# geiger_lora_edit3.net
KiCad netlist of a schematic drawn in EAGLE
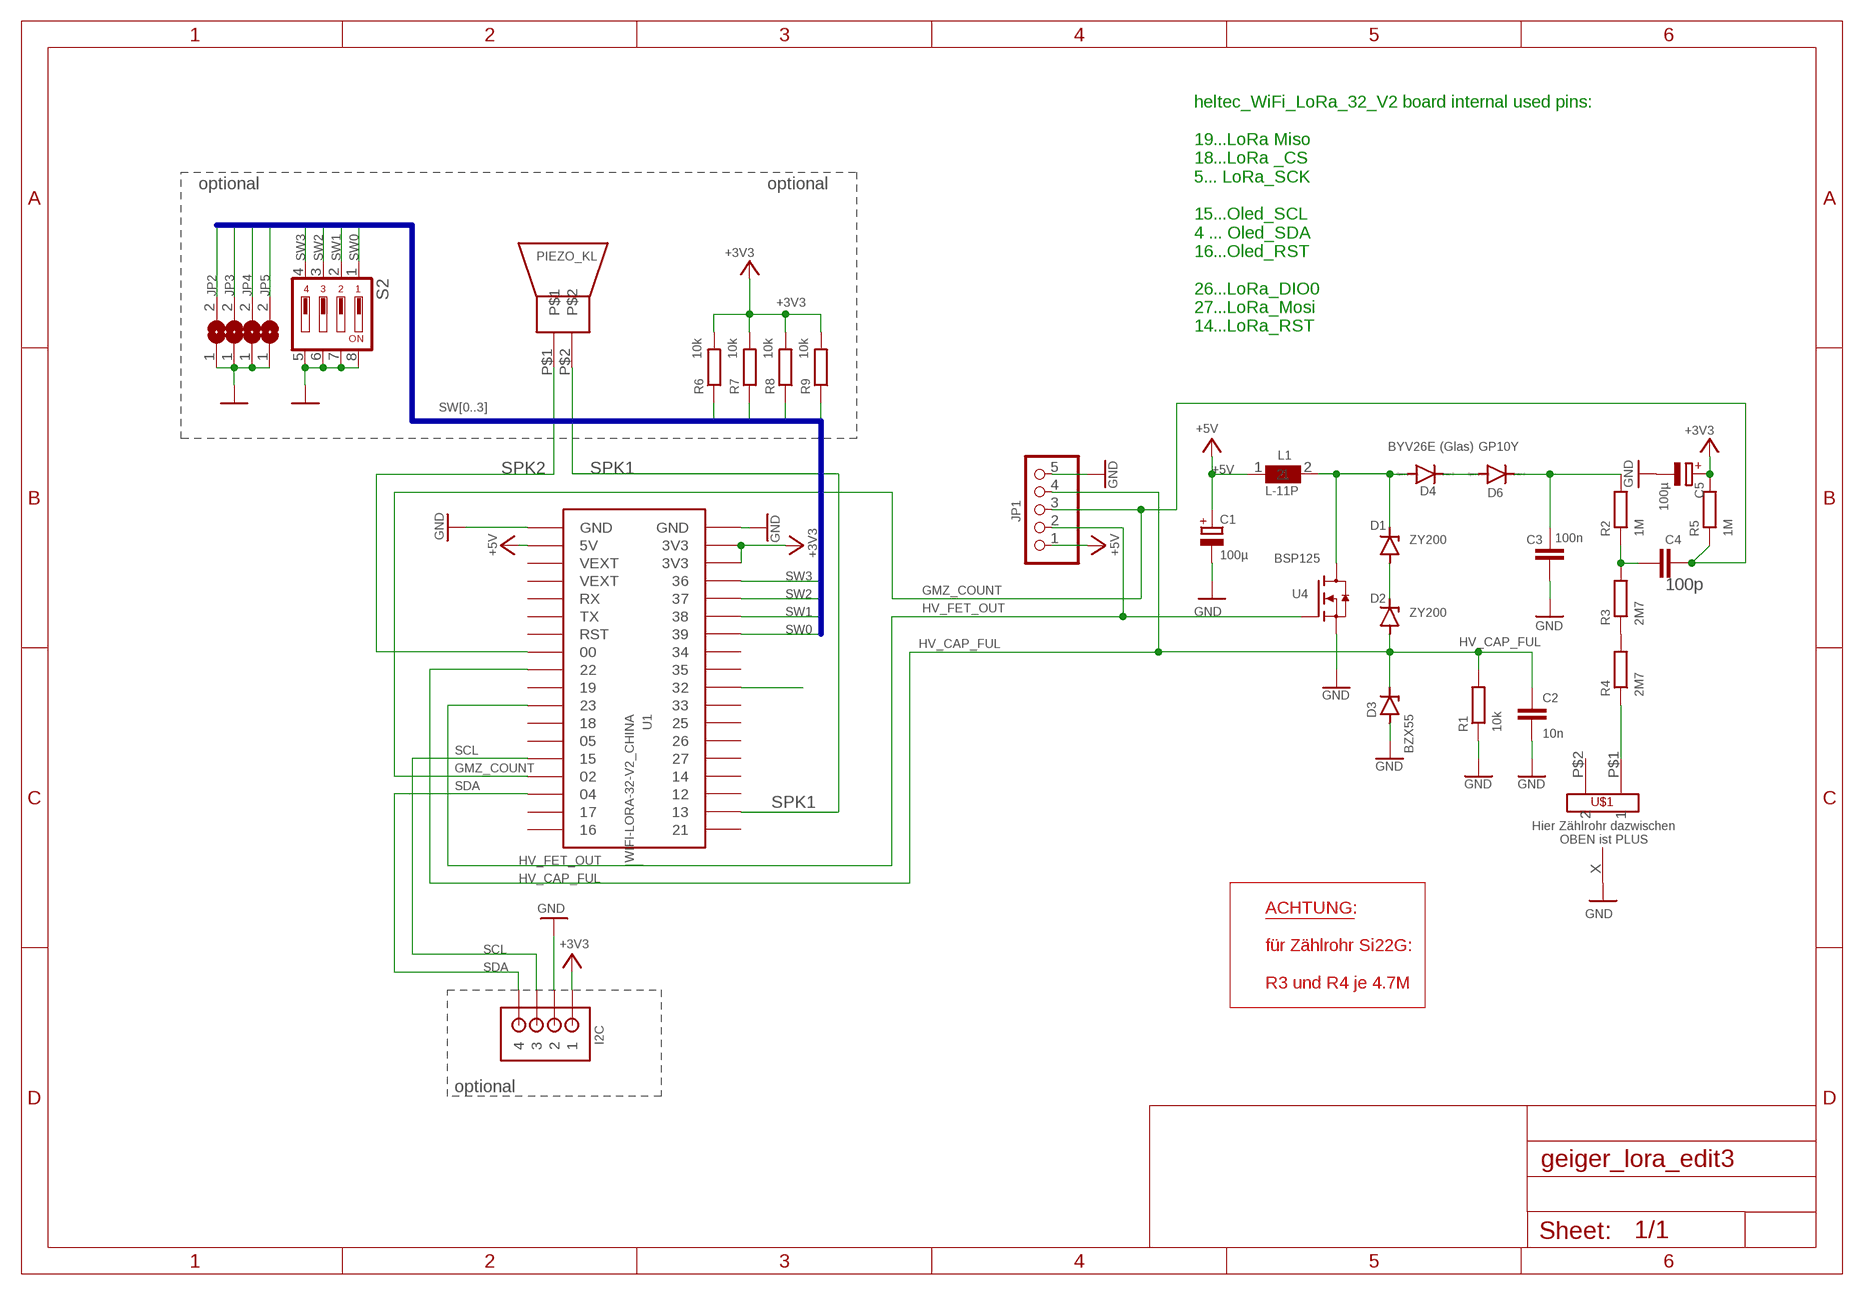
[diagram p0: schematic, sheet 1]

(export (version "E")
  (design (tool "Eeschema 10.0.6"))
  (components
    (comp (ref "C1")
      (value "100µ")
      (footprint "eagle-import:E2-5")
      (libsource (lib "eagle-import") (part "CPOL-EUE2-5"))
    )
    (comp (ref "C2")
      (value "10n")
      (footprint "eagle-import:C050-035X075")
      (libsource (lib "eagle-import") (part "C-EU050-035X075"))
    )
    (comp (ref "C3")
      (value "100n")
      (footprint "eagle-import:C150-072X183")
      (libsource (lib "eagle-import") (part "C-EU150-072X183"))
    )
    (comp (ref "C4")
      (value "100p")
      (footprint "eagle-import:C050-045X075")
      (libsource (lib "eagle-import") (part "C-EU050-045X075"))
    )
    (comp (ref "C5")
      (value "100µ")
      (footprint "eagle-import:E2-5")
      (libsource (lib "eagle-import") (part "CPOL-EUE2-5"))
    )
    (comp (ref "D1")
      (value "ZY200")
      (footprint "eagle-import:DO41Z10")
      (libsource (lib "eagle-import") (part "ZENER-DIODEDO41Z10"))
    )
    (comp (ref "D2")
      (value "ZY200")
      (footprint "eagle-import:DO41Z10")
      (libsource (lib "eagle-import") (part "ZENER-DIODEDO41Z10"))
    )
    (comp (ref "D3")
      (value "BZX55")
      (footprint "eagle-import:DO35Z10")
      (libsource (lib "eagle-import") (part "BZX55"))
    )
    (comp (ref "D4")
      (value "BYV26E (Glas)")
      (footprint "eagle-import:DO41-10")
      (libsource (lib "eagle-import") (part "1N4004"))
    )
    (comp (ref "D6")
      (value "GP10Y")
      (footprint "eagle-import:DO41-10")
      (libsource (lib "eagle-import") (part "1N4004"))
    )
    (comp (ref "I2C")
      (value "B4B-ZRSIDE_ENTRY")
      (footprint "eagle-import:S4B-ZR")
      (libsource (lib "eagle-import") (part "B4B-ZRSIDE_ENTRY"))
    )
    (comp (ref "JP1")
      (value "PINHD-1X5")
      (footprint "eagle-import:1X05")
      (libsource (lib "eagle-import") (part "PINHD-1X5"))
    )
    (comp (ref "JP2")
      (value "Jumper")
      (footprint "eagle-import:SJ")
      (libsource (lib "eagle-import") (part "SJ"))
    )
    (comp (ref "JP3") (value "SJ") (footprint "eagle-import:SJ") (libsource (lib "eagle-import") (part "SJ")))
    (comp (ref "JP4") (value "SJ") (footprint "eagle-import:SJ") (libsource (lib "eagle-import") (part "SJ")))
    (comp (ref "JP5") (value "SJ") (footprint "eagle-import:SJ") (libsource (lib "eagle-import") (part "SJ")))
    (comp (ref "L1")
      (value "L-11P")
      (footprint "eagle-import:L-11P")
      (libsource (lib "eagle-import") (part "L-11P"))
    )
    (comp (ref "PIEZO_KL")
      (value "PIEPSER")
      (footprint "eagle-import:PIEPSER")
      (libsource (lib "eagle-import") (part "PIEPSER"))
    )
    (comp (ref "R1")
      (value "10k")
      (footprint "eagle-import:0207_10")
      (libsource (lib "eagle-import") (part "R-EU_0207/10"))
    )
    (comp (ref "R2")
      (value "1M")
      (footprint "eagle-import:0207_10")
      (libsource (lib "eagle-import") (part "R-EU_0207/10"))
    )
    (comp (ref "R3")
      (value "2M7")
      (footprint "eagle-import:0207_10")
      (libsource (lib "eagle-import") (part "R-EU_0207/10"))
    )
    (comp (ref "R4")
      (value "2M7")
      (footprint "eagle-import:0207_10")
      (libsource (lib "eagle-import") (part "R-EU_0207/10"))
    )
    (comp (ref "R5")
      (value "1M")
      (footprint "eagle-import:0207_10")
      (libsource (lib "eagle-import") (part "R-EU_0207/10"))
    )
    (comp (ref "R6")
      (value "10k")
      (footprint "eagle-import:M0805")
      (libsource (lib "eagle-import") (part "R-EU_M0805"))
    )
    (comp (ref "R7")
      (value "10k")
      (footprint "eagle-import:M0805")
      (libsource (lib "eagle-import") (part "R-EU_M0805"))
    )
    (comp (ref "R8")
      (value "10k")
      (footprint "eagle-import:M0805")
      (libsource (lib "eagle-import") (part "R-EU_M0805"))
    )
    (comp (ref "R9")
      (value "10k")
      (footprint "eagle-import:M0805")
      (libsource (lib "eagle-import") (part "R-EU_M0805"))
    )
    (comp (ref "S2")
      (value "DIP04YL")
      (footprint "eagle-import:DIP04YL")
      (libsource (lib "eagle-import") (part "DIP04YL"))
    )
    (comp (ref "U$1")
      (value "FUSE_HOLDER")
      (footprint "eagle-import:FUSE_HOLDER")
      (libsource (lib "eagle-import") (part "FUSE_HOLDER"))
    )
    (comp (ref "U$5")
      (value "ONE_PAD")
      (footprint "eagle-import:ONE_PAD")
      (libsource (lib "eagle-import") (part "ONE_PAD"))
    )
    (comp (ref "U1")
      (value "WIFI-LORA-32-V2_CHINA")
      (footprint "eagle-import:2.54MM_2X18_CHINA")
      (libsource (lib "eagle-import") (part "WIFI-LORA-32-V2_CHINA"))
    )
    (comp (ref "U4")
      (value "BSP125")
      (footprint "eagle-import:SOT223")
      (libsource (lib "eagle-import") (part "BSP125"))
    )
  )
  (nets
    (net (code "1") (name "+3V3") (class "Default")
      (node (ref "C5") (pin "+") (pinfunction "+_+") (pintype "passive"))
      (node (ref "I2C") (pin "1") (pinfunction "1_1") (pintype "bidirectional"))
      (node (ref "R5") (pin "2") (pinfunction "2_2") (pintype "passive"))
      (node (ref "R6") (pin "2") (pinfunction "2_2") (pintype "passive"))
      (node (ref "R7") (pin "2") (pinfunction "2_2") (pintype "passive"))
      (node (ref "R8") (pin "2") (pinfunction "2_2") (pintype "passive"))
      (node (ref "R9") (pin "2") (pinfunction "2_2") (pintype "passive"))
      (node (ref "U1") (pin "P$34") (pinfunction "3V3_P$34") (pintype "power_in"))
      (node (ref "U1") (pin "P$35") (pinfunction "3V3_P$35") (pintype "power_in"))
    )
    (net (code "2") (name "+5V") (class "Default")
      (node (ref "C1") (pin "+") (pinfunction "+_+") (pintype "passive"))
      (node (ref "JP1") (pin "1") (pinfunction "1_1") (pintype "passive"))
      (node (ref "L1") (pin "1") (pinfunction "1_1") (pintype "bidirectional"))
      (node (ref "U1") (pin "P$2") (pinfunction "5V_P$2") (pintype "power_in"))
    )
    (net (code "3") (name "/GMZ_COUNT") (class "Default")
      (node (ref "C4") (pin "2") (pinfunction "2_2") (pintype "passive"))
      (node (ref "JP1") (pin "3") (pinfunction "3_3") (pintype "passive"))
      (node (ref "R5") (pin "1") (pinfunction "1_1") (pintype "passive"))
      (node (ref "U1") (pin "P$15") (pinfunction "02_P$15") (pintype "bidirectional"))
    )
    (net (code "4") (name "/HV_CAP_FUL") (class "Default")
      (node (ref "C2") (pin "1") (pinfunction "1_1") (pintype "passive"))
      (node (ref "D2") (pin "A") (pinfunction "A_A") (pintype "passive"))
      (node (ref "D3") (pin "C") (pinfunction "C_C") (pintype "passive"))
      (node (ref "JP1") (pin "4") (pinfunction "4_4") (pintype "passive"))
      (node (ref "R1") (pin "2") (pinfunction "2_2") (pintype "passive"))
      (node (ref "U1") (pin "P$9") (pinfunction "22_P$9") (pintype "bidirectional"))
    )
    (net (code "5") (name "/HV_FET_OUT") (class "Default")
      (node (ref "JP1") (pin "2") (pinfunction "2_2") (pintype "passive"))
      (node (ref "U1") (pin "P$11") (pinfunction "23_P$11") (pintype "bidirectional"))
      (node (ref "U4") (pin "1") (pinfunction "G_1") (pintype "passive"))
    )
    (net (code "6") (name "/SCL") (class "Default")
      (node (ref "I2C") (pin "3") (pinfunction "3_3") (pintype "bidirectional"))
      (node (ref "U1") (pin "P$14") (pinfunction "15_P$14") (pintype "bidirectional"))
    )
    (net (code "7") (name "/SDA") (class "Default")
      (node (ref "I2C") (pin "4") (pinfunction "4_4") (pintype "bidirectional"))
      (node (ref "U1") (pin "P$16") (pinfunction "04_P$16") (pintype "bidirectional"))
    )
    (net (code "8") (name "/SPK1") (class "Default")
      (node (ref "PIEZO_KL") (pin "P$2") (pinfunction "P$2_P$2") (pintype "bidirectional"))
      (node (ref "U1") (pin "P$20") (pinfunction "13_P$20") (pintype "bidirectional"))
    )
    (net (code "9") (name "/SPK2") (class "Default")
      (node (ref "PIEZO_KL") (pin "P$1") (pinfunction "P$1_P$1") (pintype "bidirectional"))
      (node (ref "U1") (pin "P$8") (pinfunction "00_P$8") (pintype "bidirectional"))
    )
    (net (code "10") (name "/SW0") (class "Default")
      (node (ref "JP5") (pin "2") (pinfunction "2_2") (pintype "passive"))
      (node (ref "R6") (pin "1") (pinfunction "1_1") (pintype "passive"))
      (node (ref "S2") (pin "1") (pinfunction "1_1") (pintype "passive"))
      (node (ref "U1") (pin "P$30") (pinfunction "39_P$30") (pintype "bidirectional"))
    )
    (net (code "11") (name "/SW1") (class "Default")
      (node (ref "JP4") (pin "2") (pinfunction "2_2") (pintype "passive"))
      (node (ref "R7") (pin "1") (pinfunction "1_1") (pintype "passive"))
      (node (ref "S2") (pin "2") (pinfunction "2_2") (pintype "passive"))
      (node (ref "U1") (pin "P$31") (pinfunction "38_P$31") (pintype "bidirectional"))
    )
    (net (code "12") (name "/SW2") (class "Default")
      (node (ref "JP3") (pin "2") (pinfunction "2_2") (pintype "passive"))
      (node (ref "R8") (pin "1") (pinfunction "1_1") (pintype "passive"))
      (node (ref "S2") (pin "3") (pinfunction "3_3") (pintype "passive"))
      (node (ref "U1") (pin "P$32") (pinfunction "37_P$32") (pintype "bidirectional"))
    )
    (net (code "13") (name "/SW3") (class "Default")
      (node (ref "JP2") (pin "2") (pinfunction "2_2") (pintype "passive"))
      (node (ref "R9") (pin "1") (pinfunction "1_1") (pintype "passive"))
      (node (ref "S2") (pin "4") (pinfunction "4_4") (pintype "passive"))
      (node (ref "U1") (pin "P$33") (pinfunction "36_P$33") (pintype "bidirectional"))
    )
    (net (code "15") (name "/VEXT") (class "Default")
      (node (ref "U1") (pin "P$3") (pinfunction "VEXT_P$3") (pintype "power_in"))
    )
    (net (code "16") (name "GND") (class "Default")
      (node (ref "C1") (pin "-") (pinfunction "-_-") (pintype "passive"))
      (node (ref "C2") (pin "2") (pinfunction "2_2") (pintype "passive"))
      (node (ref "C3") (pin "2") (pinfunction "2_2") (pintype "passive"))
      (node (ref "C5") (pin "-") (pinfunction "-_-") (pintype "passive"))
      (node (ref "D3") (pin "A") (pinfunction "A_A") (pintype "passive"))
      (node (ref "I2C") (pin "2") (pinfunction "2_2") (pintype "bidirectional"))
      (node (ref "JP1") (pin "5") (pinfunction "5_5") (pintype "passive"))
      (node (ref "JP2") (pin "1") (pinfunction "1_1") (pintype "passive"))
      (node (ref "JP3") (pin "1") (pinfunction "1_1") (pintype "passive"))
      (node (ref "JP4") (pin "1") (pinfunction "1_1") (pintype "passive"))
      (node (ref "JP5") (pin "1") (pinfunction "1_1") (pintype "passive"))
      (node (ref "R1") (pin "1") (pinfunction "1_1") (pintype "passive"))
      (node (ref "S2") (pin "5") (pinfunction "5_5") (pintype "passive"))
      (node (ref "S2") (pin "6") (pinfunction "6_6") (pintype "passive"))
      (node (ref "S2") (pin "7") (pinfunction "7_7") (pintype "passive"))
      (node (ref "S2") (pin "8") (pinfunction "8_8") (pintype "passive"))
      (node (ref "U$5") (pin "X") (pinfunction "P$1_X") (pintype "bidirectional"))
      (node (ref "U1") (pin "P$1") (pinfunction "GND_P$1") (pintype "power_in"))
      (node (ref "U1") (pin "P$36") (pinfunction "GND_P$36") (pintype "power_in"))
      (node (ref "U4") (pin "3") (pinfunction "S_3") (pintype "passive"))
    )
    (net (code "17") (name "Net-(C3-Pad1)") (class "Default")
      (node (ref "C3") (pin "1") (pinfunction "1_1") (pintype "passive"))
      (node (ref "D6") (pin "C") (pinfunction "C_C") (pintype "passive"))
      (node (ref "R2") (pin "2") (pinfunction "2_2") (pintype "passive"))
    )
    (net (code "18") (name "Net-(C4-Pad1)") (class "Default")
      (node (ref "C4") (pin "1") (pinfunction "1_1") (pintype "passive"))
      (node (ref "R2") (pin "1") (pinfunction "1_1") (pintype "passive"))
      (node (ref "R3") (pin "2") (pinfunction "2_2") (pintype "passive"))
    )
    (net (code "19") (name "Net-(D1-PadA)") (class "Default")
      (node (ref "D1") (pin "A") (pinfunction "A_A") (pintype "passive"))
      (node (ref "D2") (pin "C") (pinfunction "C_C") (pintype "passive"))
    )
    (net (code "20") (name "Net-(D1-PadC)") (class "Default")
      (node (ref "D1") (pin "C") (pinfunction "C_C") (pintype "passive"))
      (node (ref "D4") (pin "A") (pinfunction "A_A") (pintype "passive"))
      (node (ref "L1") (pin "2") (pinfunction "2_2") (pintype "bidirectional"))
      (node (ref "U4") (pin "2") (pinfunction "D_2") (pintype "passive"))
      (node (ref "U4") (pin "4") (pinfunction "D_4") (pintype "passive"))
    )
    (net (code "21") (name "Net-(D4-PadC)") (class "Default")
      (node (ref "D4") (pin "C") (pinfunction "C_C") (pintype "passive"))
      (node (ref "D6") (pin "A") (pinfunction "A_A") (pintype "passive"))
    )
    (net (code "22") (name "Net-(R3-Pad1)") (class "Default")
      (node (ref "R3") (pin "1") (pinfunction "1_1") (pintype "passive"))
      (node (ref "R4") (pin "2") (pinfunction "2_2") (pintype "passive"))
    )
    (net (code "23") (name "Net-(U$1-1)") (class "Default")
      (node (ref "R4") (pin "1") (pinfunction "1_1") (pintype "passive"))
      (node (ref "U$1") (pin "P$1") (pinfunction "1_P$1") (pintype "bidirectional"))
    )
    (net (code "24") (name "unconnected-(U$1-2-PadP$2)") (class "Default")
      (node (ref "U$1") (pin "P$2") (pinfunction "2_P$2") (pintype "bidirectional"))
    )
    (net (code "25") (name "unconnected-(U1-05-PadP$13)") (class "Default")
      (node (ref "U1") (pin "P$13") (pinfunction "05_P$13") (pintype "bidirectional"))
    )
    (net (code "26") (name "unconnected-(U1-12-PadP$21)") (class "Default")
      (node (ref "U1") (pin "P$21") (pinfunction "12_P$21") (pintype "bidirectional"))
    )
    (net (code "27") (name "unconnected-(U1-14-PadP$22)") (class "Default")
      (node (ref "U1") (pin "P$22") (pinfunction "14_P$22") (pintype "bidirectional"))
    )
    (net (code "28") (name "unconnected-(U1-16-PadP$18)") (class "Default")
      (node (ref "U1") (pin "P$18") (pinfunction "16_P$18") (pintype "bidirectional"))
    )
    (net (code "29") (name "unconnected-(U1-17-PadP$17)") (class "Default")
      (node (ref "U1") (pin "P$17") (pinfunction "17_P$17") (pintype "bidirectional"))
    )
    (net (code "30") (name "unconnected-(U1-18-PadP$12)") (class "Default")
      (node (ref "U1") (pin "P$12") (pinfunction "18_P$12") (pintype "bidirectional"))
    )
    (net (code "31") (name "unconnected-(U1-19-PadP$10)") (class "Default")
      (node (ref "U1") (pin "P$10") (pinfunction "19_P$10") (pintype "bidirectional"))
    )
    (net (code "32") (name "unconnected-(U1-21-PadP$19)") (class "Default")
      (node (ref "U1") (pin "P$19") (pinfunction "21_P$19") (pintype "bidirectional"))
    )
    (net (code "33") (name "unconnected-(U1-25-PadP$25)") (class "Default")
      (node (ref "U1") (pin "P$25") (pinfunction "25_P$25") (pintype "bidirectional"))
    )
    (net (code "34") (name "unconnected-(U1-26-PadP$24)") (class "Default")
      (node (ref "U1") (pin "P$24") (pinfunction "26_P$24") (pintype "bidirectional"))
    )
    (net (code "35") (name "unconnected-(U1-27-PadP$23)") (class "Default")
      (node (ref "U1") (pin "P$23") (pinfunction "27_P$23") (pintype "bidirectional"))
    )
    (net (code "36") (name "unconnected-(U1-32-PadP$27)") (class "Default")
      (node (ref "U1") (pin "P$27") (pinfunction "32_P$27") (pintype "bidirectional"))
    )
    (net (code "37") (name "unconnected-(U1-33-PadP$26)") (class "Default")
      (node (ref "U1") (pin "P$26") (pinfunction "33_P$26") (pintype "bidirectional"))
    )
    (net (code "38") (name "unconnected-(U1-34-PadP$29)") (class "Default")
      (node (ref "U1") (pin "P$29") (pinfunction "34_P$29") (pintype "bidirectional"))
    )
    (net (code "39") (name "unconnected-(U1-35-PadP$28)") (class "Default")
      (node (ref "U1") (pin "P$28") (pinfunction "35_P$28") (pintype "bidirectional"))
    )
    (net (code "40") (name "unconnected-(U1-RST-PadP$7)") (class "Default")
      (node (ref "U1") (pin "P$7") (pinfunction "RST_P$7") (pintype "bidirectional"))
    )
    (net (code "41") (name "unconnected-(U1-RX-PadP$5)") (class "Default")
      (node (ref "U1") (pin "P$5") (pinfunction "RX_P$5") (pintype "bidirectional"))
    )
    (net (code "42") (name "unconnected-(U1-TX-PadP$6)") (class "Default")
      (node (ref "U1") (pin "P$6") (pinfunction "TX_P$6") (pintype "bidirectional"))
    )
    (net (code "43") (name "unconnected-(U1-VEXT-PadP$4)") (class "Default")
      (node (ref "U1") (pin "P$4") (pinfunction "VEXT_P$4") (pintype "bidirectional"))
    )
  )
)
